# Power.net
KiCad netlist of a schematic drawn in Altium Designer
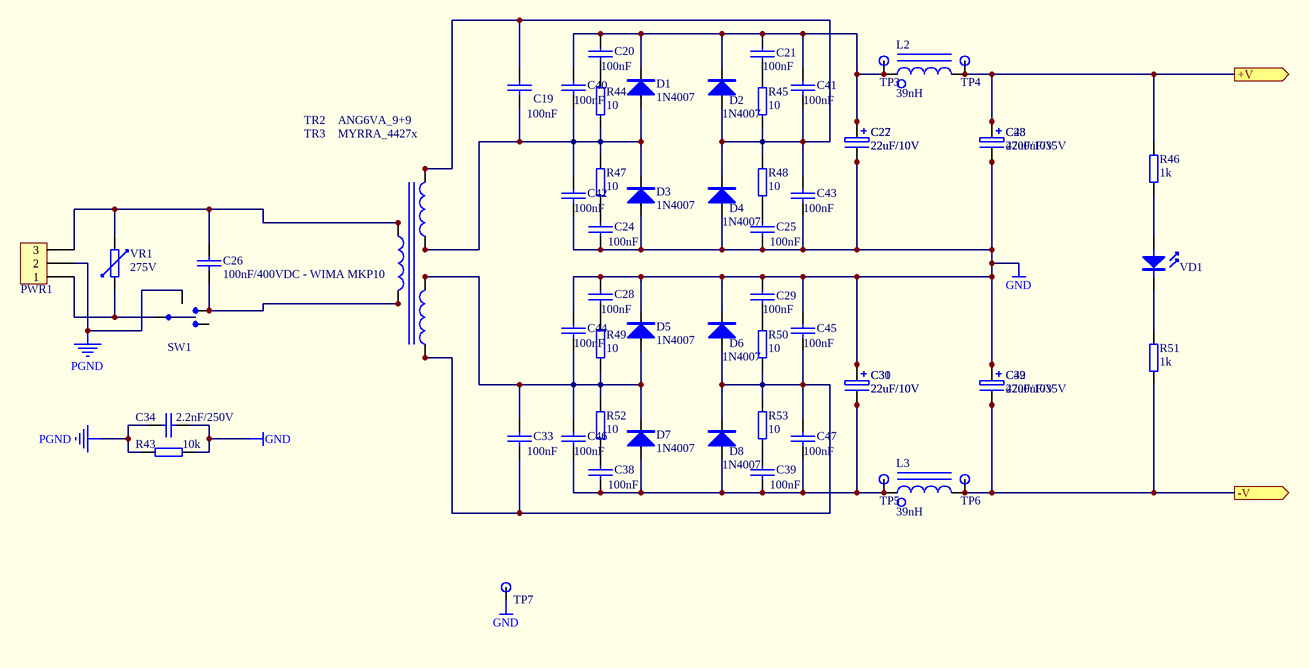
[diagram p0: Power.SchDoc]

(export (version "E")
  (design (tool "Eeschema 10.0.6"))
  (components
    (comp (ref "C19")
      (value "100nF")
      (footprint "CAP_C200-1")
      (description "Capacitor")
      (libsource (lib "ivan") (part "CAP"))
    )
    (comp (ref "C20")
      (value "100nF")
      (footprint "CAP_C200")
      (description "Capacitor")
      (libsource (lib "ivan") (part "CAP"))
    )
    (comp (ref "C21")
      (value "100nF")
      (footprint "CAP_C200")
      (description "Capacitor")
      (libsource (lib "ivan") (part "CAP"))
    )
    (comp (ref "C22")
      (value "22uF/10V")
      (footprint "CAP_EC10x20")
      (description "Electrolytic Capacitor")
      (libsource (lib "MainSchlib") (part "ELECTRO1"))
    )
    (comp (ref "C23")
      (value "4700uF/35V")
      (footprint "CAP_EC22x40")
      (description "Electrolytic Capacitor")
      (libsource (lib "ivan") (part "ELECTRO1"))
    )
    (comp (ref "C24")
      (value "100nF")
      (footprint "CAP_C200")
      (description "Capacitor")
      (libsource (lib "ivan") (part "CAP"))
    )
    (comp (ref "C25")
      (value "100nF")
      (footprint "CAP_C200")
      (description "Capacitor")
      (libsource (lib "ivan") (part "CAP"))
    )
    (comp (ref "C26")
      (value "100nF/400VDC - WIMA MKP10")
      (footprint "CAP_5.7x10.3RM7.5")
      (description "Capacitor")
      (libsource (lib "*") (part "CAP"))
    )
    (comp (ref "C27")
      (value "22uF/10V")
      (footprint "CAP_EC22x40")
      (description "Electrolytic Capacitor")
      (libsource (lib "MainSchlib") (part "ELECTRO1"))
    )
    (comp (ref "C28")
      (value "100nF")
      (footprint "CAP_C200")
      (description "Capacitor")
      (libsource (lib "ivan") (part "CAP"))
    )
    (comp (ref "C29")
      (value "100nF")
      (footprint "CAP_C200")
      (description "Capacitor")
      (libsource (lib "ivan") (part "CAP"))
    )
    (comp (ref "C30")
      (value "22uF/10V")
      (footprint "CAP_EC10x20")
      (description "Electrolytic Capacitor")
      (libsource (lib "MainSchlib") (part "ELECTRO1"))
    )
    (comp (ref "C31")
      (value "22uF/10V")
      (footprint "CAP_EC22x40")
      (description "Electrolytic Capacitor")
      (libsource (lib "MainSchlib") (part "ELECTRO1"))
    )
    (comp (ref "C32")
      (value "4700uF/35V")
      (footprint "CAP_EC22x40")
      (description "Electrolytic Capacitor")
      (libsource (lib "ivan") (part "ELECTRO1"))
    )
    (comp (ref "C33")
      (value "100nF")
      (footprint "CAP_C200-1")
      (description "Capacitor")
      (libsource (lib "ivan") (part "CAP"))
    )
    (comp (ref "C34")
      (value "2.2nF/250V")
      (footprint "CAP_5.7x10.3RM7.5")
      (description "Capacitor")
      (libsource (lib "*") (part "CAP"))
    )
    (comp (ref "C38")
      (value "100nF")
      (footprint "CAP_C200")
      (description "Capacitor")
      (libsource (lib "ivan") (part "CAP"))
    )
    (comp (ref "C39")
      (value "100nF")
      (footprint "CAP_C200")
      (description "Capacitor")
      (libsource (lib "ivan") (part "CAP"))
    )
    (comp (ref "C40")
      (value "100nF")
      (footprint "CAP_C200")
      (description "Capacitor")
      (libsource (lib "ivan") (part "CAP"))
    )
    (comp (ref "C41")
      (value "100nF")
      (footprint "CAP_C200")
      (description "Capacitor")
      (libsource (lib "ivan") (part "CAP"))
    )
    (comp (ref "C42")
      (value "100nF")
      (footprint "CAP_C200")
      (description "Capacitor")
      (libsource (lib "ivan") (part "CAP"))
    )
    (comp (ref "C43")
      (value "100nF")
      (footprint "CAP_C200")
      (description "Capacitor")
      (libsource (lib "ivan") (part "CAP"))
    )
    (comp (ref "C44")
      (value "100nF")
      (footprint "CAP_C200")
      (description "Capacitor")
      (libsource (lib "ivan") (part "CAP"))
    )
    (comp (ref "C45")
      (value "100nF")
      (footprint "CAP_C200")
      (description "Capacitor")
      (libsource (lib "ivan") (part "CAP"))
    )
    (comp (ref "C46")
      (value "100nF")
      (footprint "CAP_C200")
      (description "Capacitor")
      (libsource (lib "ivan") (part "CAP"))
    )
    (comp (ref "C47")
      (value "100nF")
      (footprint "CAP_C200")
      (description "Capacitor")
      (libsource (lib "ivan") (part "CAP"))
    )
    (comp (ref "C48")
      (value "22uF/10V")
      (footprint "CAP_EC10x20")
      (description "Electrolytic Capacitor")
      (libsource (lib "MainSchlib") (part "ELECTRO1"))
    )
    (comp (ref "C49")
      (value "22uF/10V")
      (footprint "CAP_EC10x20")
      (description "Electrolytic Capacitor")
      (libsource (lib "MainSchlib") (part "ELECTRO1"))
    )
    (comp (ref "D1")
      (value "1N4007")
      (footprint "DIODE_D400")
      (description "Diode")
      (libsource (lib "ivan") (part "DIODE"))
    )
    (comp (ref "D2")
      (value "1N4007")
      (footprint "DIODE_D400")
      (description "Diode")
      (libsource (lib "ivan") (part "DIODE"))
    )
    (comp (ref "D3")
      (value "1N4007")
      (footprint "DIODE_D400")
      (description "Diode")
      (libsource (lib "ivan") (part "DIODE"))
    )
    (comp (ref "D4")
      (value "1N4007")
      (footprint "DIODE_D400")
      (description "Diode")
      (libsource (lib "ivan") (part "DIODE"))
    )
    (comp (ref "D5")
      (value "1N4007")
      (footprint "DIODE_D400")
      (description "Diode")
      (libsource (lib "ivan") (part "DIODE"))
    )
    (comp (ref "D6")
      (value "1N4007")
      (footprint "DIODE_D400")
      (description "Diode")
      (libsource (lib "ivan") (part "DIODE"))
    )
    (comp (ref "D7")
      (value "1N4007")
      (footprint "DIODE_D400")
      (description "Diode")
      (libsource (lib "ivan") (part "DIODE"))
    )
    (comp (ref "D8")
      (value "1N4007")
      (footprint "DIODE_D400")
      (description "Diode")
      (libsource (lib "ivan") (part "DIODE"))
    )
    (comp (ref "L2")
      (value "39nH")
      (footprint "IND_SRI1205")
      (libsource (lib "MainSchlib") (part "INDUCTOR IRON1"))
    )
    (comp (ref "L3")
      (value "39nH")
      (footprint "IND_SRI1205")
      (libsource (lib "MainSchlib") (part "INDUCTOR IRON1"))
    )
    (comp (ref "PWR1")
      (value "CON3")
      (footprint "CON_TOP_3P")
      (description "Connector")
      (libsource (lib "*") (part "CON3"))
    )
    (comp (ref "R43")
      (value "10k")
      (footprint "RES_R400")
      (description "Resistor")
      (libsource (lib "*") (part "RES"))
    )
    (comp (ref "R44")
      (value "10")
      (footprint "RES_R400")
      (description "Resistor")
      (libsource (lib "*") (part "RES"))
    )
    (comp (ref "R45")
      (value "10")
      (footprint "RES_R400")
      (description "Resistor")
      (libsource (lib "*") (part "RES"))
    )
    (comp (ref "R46")
      (value "1k")
      (footprint "RES_R400")
      (description "Resistor")
      (libsource (lib "MainSchlib") (part "RES"))
    )
    (comp (ref "R47")
      (value "10")
      (footprint "RES_R400")
      (description "Resistor")
      (libsource (lib "*") (part "RES"))
    )
    (comp (ref "R48")
      (value "10")
      (footprint "RES_R400")
      (description "Resistor")
      (libsource (lib "*") (part "RES"))
    )
    (comp (ref "R49")
      (value "10")
      (footprint "RES_R400")
      (description "Resistor")
      (libsource (lib "*") (part "RES"))
    )
    (comp (ref "R50")
      (value "10")
      (footprint "RES_R400")
      (description "Resistor")
      (libsource (lib "*") (part "RES"))
    )
    (comp (ref "R51")
      (value "1k")
      (footprint "RES_R400")
      (description "Resistor")
      (libsource (lib "MainSchlib") (part "RES"))
    )
    (comp (ref "R52")
      (value "10")
      (footprint "RES_R400")
      (description "Resistor")
      (libsource (lib "*") (part "RES"))
    )
    (comp (ref "R53")
      (value "10")
      (footprint "RES_R400")
      (description "Resistor")
      (libsource (lib "*") (part "RES"))
    )
    (comp (ref "SW1") (value "SW") (footprint "SW_250VAC1.5A") (libsource (lib "*") (part "SW_2WAY")))
    (comp (ref "TP3")
      (value "TESTPAD")
      (footprint "MISC_PAD-36/65")
      (libsource (lib "MainSchlib") (part "TESTPAD"))
    )
    (comp (ref "TP4")
      (value "TESTPAD")
      (footprint "MISC_PAD-36/65")
      (libsource (lib "MainSchlib") (part "TESTPAD"))
    )
    (comp (ref "TP5")
      (value "TESTPAD")
      (footprint "MISC_PAD-36/65")
      (libsource (lib "MainSchlib") (part "TESTPAD"))
    )
    (comp (ref "TP6")
      (value "TESTPAD")
      (footprint "MISC_PAD-36/65")
      (libsource (lib "MainSchlib") (part "TESTPAD"))
    )
    (comp (ref "TP7")
      (value "TESTPAD")
      (footprint "MISC_PAD-36/65")
      (libsource (lib "MainSchlib") (part "TESTPAD"))
    )
    (comp (ref "TR2")
      (value "ANG6VA_9+9")
      (footprint "TRAF_ANG6VA")
      (libsource (lib "*") (part "TRAF_ANG6VAx+x"))
    )
    (comp (ref "TR3")
      (value "MYRRA_4427x")
      (footprint "TRAF_MYRRA_10VA")
      (libsource (lib "MainSchlib") (part "TRAF_MYRRA_10VA_D"))
    )
    (comp (ref "VD1")
      (value "LED")
      (footprint "LED_5MM")
      (description "LED, 3mm")
      (libsource (lib "MainSchlib") (part "LED"))
    )
    (comp (ref "VR1")
      (value "275V")
      (footprint "MISC_Varistor")
      (description "Resistor")
      (libsource (lib "*") (part "VARISTOR"))
    )
  )
  (nets
    (net (code "1") (name "/+V") (class "Default")
      (node (ref "C23") (pin "1") (pinfunction "1_1") (pintype "passive"))
      (node (ref "C48") (pin "1") (pinfunction "1_1") (pintype "passive"))
      (node (ref "L2") (pin "2") (pinfunction "2_2") (pintype "passive"))
      (node (ref "R46") (pin "2") (pintype "passive"))
      (node (ref "TP4") (pin "1") (pinfunction "1_1") (pintype "passive"))
    )
    (net (code "2") (name "/-V") (class "Default")
      (node (ref "C32") (pin "2") (pinfunction "2_2") (pintype "passive"))
      (node (ref "C49") (pin "2") (pinfunction "2_2") (pintype "passive"))
      (node (ref "L3") (pin "2") (pinfunction "2_2") (pintype "passive"))
      (node (ref "R51") (pin "1") (pintype "passive"))
      (node (ref "TP6") (pin "1") (pinfunction "1_1") (pintype "passive"))
    )
    (net (code "3") (name "GND") (class "Default")
      (node (ref "C22") (pin "2") (pinfunction "2_2") (pintype "passive"))
      (node (ref "C23") (pin "2") (pinfunction "2_2") (pintype "passive"))
      (node (ref "C24") (pin "2") (pinfunction "2_2") (pintype "passive"))
      (node (ref "C25") (pin "2") (pinfunction "2_2") (pintype "passive"))
      (node (ref "C27") (pin "2") (pinfunction "2_2") (pintype "passive"))
      (node (ref "C28") (pin "1") (pinfunction "1_1") (pintype "passive"))
      (node (ref "C29") (pin "1") (pinfunction "1_1") (pintype "passive"))
      (node (ref "C30") (pin "1") (pinfunction "1_1") (pintype "passive"))
      (node (ref "C31") (pin "1") (pinfunction "1_1") (pintype "passive"))
      (node (ref "C32") (pin "1") (pinfunction "1_1") (pintype "passive"))
      (node (ref "C34") (pin "2") (pinfunction "2_2") (pintype "passive"))
      (node (ref "C42") (pin "2") (pinfunction "2_2") (pintype "passive"))
      (node (ref "C43") (pin "2") (pinfunction "2_2") (pintype "passive"))
      (node (ref "C44") (pin "1") (pinfunction "1_1") (pintype "passive"))
      (node (ref "C45") (pin "1") (pinfunction "1_1") (pintype "passive"))
      (node (ref "C48") (pin "2") (pinfunction "2_2") (pintype "passive"))
      (node (ref "C49") (pin "1") (pinfunction "1_1") (pintype "passive"))
      (node (ref "D3") (pin "1") (pinfunction "A_1") (pintype "passive"))
      (node (ref "D4") (pin "1") (pinfunction "A_1") (pintype "passive"))
      (node (ref "D5") (pin "2") (pinfunction "K_2") (pintype "passive"))
      (node (ref "D6") (pin "2") (pinfunction "K_2") (pintype "passive"))
      (node (ref "R43") (pin "2") (pintype "passive"))
      (node (ref "TP7") (pin "1") (pinfunction "1_1") (pintype "passive"))
    )
    (net (code "4") (name "Net-(C20-Pad2)") (class "Default")
      (node (ref "C20") (pin "2") (pinfunction "2_2") (pintype "passive"))
      (node (ref "R44") (pin "2") (pintype "passive"))
    )
    (net (code "5") (name "Net-(C21-Pad2)") (class "Default")
      (node (ref "C21") (pin "2") (pinfunction "2_2") (pintype "passive"))
      (node (ref "R45") (pin "2") (pintype "passive"))
    )
    (net (code "6") (name "Net-(C24-Pad1)") (class "Default")
      (node (ref "C24") (pin "1") (pinfunction "1_1") (pintype "passive"))
      (node (ref "R47") (pin "1") (pintype "passive"))
    )
    (net (code "7") (name "Net-(C25-Pad1)") (class "Default")
      (node (ref "C25") (pin "1") (pinfunction "1_1") (pintype "passive"))
      (node (ref "R48") (pin "1") (pintype "passive"))
    )
    (net (code "8") (name "Net-(C26-Pad1)") (class "Default")
      (node (ref "C26") (pin "1") (pinfunction "1_1") (pintype "passive"))
      (node (ref "SW1") (pin "3") (pinfunction "3_3") (pintype "passive"))
      (node (ref "TR2") (pin "1") (pinfunction "1_1") (pintype "passive"))
      (node (ref "TR3") (pin "6") (pinfunction "6_6") (pintype "passive"))
    )
    (net (code "9") (name "Net-(C26-Pad2)") (class "Default")
      (node (ref "C26") (pin "2") (pinfunction "2_2") (pintype "passive"))
      (node (ref "PWR1") (pin "3") (pinfunction "3_3") (pintype "passive"))
      (node (ref "TR2") (pin "5") (pinfunction "5_5") (pintype "passive"))
      (node (ref "TR3") (pin "1") (pinfunction "1_1") (pintype "passive"))
      (node (ref "VR1") (pin "1") (pintype "passive"))
    )
    (net (code "10") (name "Net-(C28-Pad2)") (class "Default")
      (node (ref "C28") (pin "2") (pinfunction "2_2") (pintype "passive"))
      (node (ref "R49") (pin "2") (pintype "passive"))
    )
    (net (code "11") (name "Net-(C29-Pad2)") (class "Default")
      (node (ref "C29") (pin "2") (pinfunction "2_2") (pintype "passive"))
      (node (ref "R50") (pin "2") (pintype "passive"))
    )
    (net (code "12") (name "Net-(C38-Pad1)") (class "Default")
      (node (ref "C38") (pin "1") (pinfunction "1_1") (pintype "passive"))
      (node (ref "R52") (pin "1") (pintype "passive"))
    )
    (net (code "13") (name "Net-(C39-Pad1)") (class "Default")
      (node (ref "C39") (pin "1") (pinfunction "1_1") (pintype "passive"))
      (node (ref "R53") (pin "1") (pintype "passive"))
    )
    (net (code "14") (name "Net-(D1-A)") (class "Default")
      (node (ref "C19") (pin "2") (pinfunction "2_2") (pintype "passive"))
      (node (ref "C40") (pin "2") (pinfunction "2_2") (pintype "passive"))
      (node (ref "C42") (pin "1") (pinfunction "1_1") (pintype "passive"))
      (node (ref "D1") (pin "1") (pinfunction "A_1") (pintype "passive"))
      (node (ref "D3") (pin "2") (pinfunction "K_2") (pintype "passive"))
      (node (ref "R44") (pin "1") (pintype "passive"))
      (node (ref "R47") (pin "2") (pintype "passive"))
      (node (ref "TR2") (pin "9") (pinfunction "9_9") (pintype "passive"))
      (node (ref "TR3") (pin "11") (pinfunction "11_11") (pintype "passive"))
    )
    (net (code "15") (name "Net-(D1-K)") (class "Default")
      (node (ref "C20") (pin "1") (pinfunction "1_1") (pintype "passive"))
      (node (ref "C21") (pin "1") (pinfunction "1_1") (pintype "passive"))
      (node (ref "C22") (pin "1") (pinfunction "1_1") (pintype "passive"))
      (node (ref "C27") (pin "1") (pinfunction "1_1") (pintype "passive"))
      (node (ref "C40") (pin "1") (pinfunction "1_1") (pintype "passive"))
      (node (ref "C41") (pin "1") (pinfunction "1_1") (pintype "passive"))
      (node (ref "D1") (pin "2") (pinfunction "K_2") (pintype "passive"))
      (node (ref "D2") (pin "2") (pinfunction "K_2") (pintype "passive"))
      (node (ref "L2") (pin "1") (pinfunction "1_1") (pintype "passive"))
      (node (ref "TP3") (pin "1") (pinfunction "1_1") (pintype "passive"))
    )
    (net (code "16") (name "Net-(D2-A)") (class "Default")
      (node (ref "C19") (pin "1") (pinfunction "1_1") (pintype "passive"))
      (node (ref "C41") (pin "2") (pinfunction "2_2") (pintype "passive"))
      (node (ref "C43") (pin "1") (pinfunction "1_1") (pintype "passive"))
      (node (ref "D2") (pin "1") (pinfunction "A_1") (pintype "passive"))
      (node (ref "D4") (pin "2") (pinfunction "K_2") (pintype "passive"))
      (node (ref "R45") (pin "1") (pintype "passive"))
      (node (ref "R48") (pin "2") (pintype "passive"))
      (node (ref "TR2") (pin "10") (pinfunction "10_10") (pintype "passive"))
      (node (ref "TR3") (pin "12") (pinfunction "12_12") (pintype "passive"))
    )
    (net (code "17") (name "Net-(D5-A)") (class "Default")
      (node (ref "C33") (pin "1") (pinfunction "1_1") (pintype "passive"))
      (node (ref "C44") (pin "2") (pinfunction "2_2") (pintype "passive"))
      (node (ref "C46") (pin "1") (pinfunction "1_1") (pintype "passive"))
      (node (ref "D5") (pin "1") (pinfunction "A_1") (pintype "passive"))
      (node (ref "D7") (pin "2") (pinfunction "K_2") (pintype "passive"))
      (node (ref "R49") (pin "1") (pintype "passive"))
      (node (ref "R52") (pin "2") (pintype "passive"))
      (node (ref "TR2") (pin "7") (pinfunction "7_7") (pintype "passive"))
      (node (ref "TR3") (pin "8") (pinfunction "8_8") (pintype "passive"))
    )
    (net (code "18") (name "Net-(D6-A)") (class "Default")
      (node (ref "C33") (pin "2") (pinfunction "2_2") (pintype "passive"))
      (node (ref "C45") (pin "2") (pinfunction "2_2") (pintype "passive"))
      (node (ref "C47") (pin "1") (pinfunction "1_1") (pintype "passive"))
      (node (ref "D6") (pin "1") (pinfunction "A_1") (pintype "passive"))
      (node (ref "D8") (pin "2") (pinfunction "K_2") (pintype "passive"))
      (node (ref "R50") (pin "1") (pintype "passive"))
      (node (ref "R53") (pin "2") (pintype "passive"))
      (node (ref "TR2") (pin "6") (pinfunction "6_6") (pintype "passive"))
      (node (ref "TR3") (pin "7") (pinfunction "7_7") (pintype "passive"))
    )
    (net (code "19") (name "Net-(D7-A)") (class "Default")
      (node (ref "C30") (pin "2") (pinfunction "2_2") (pintype "passive"))
      (node (ref "C31") (pin "2") (pinfunction "2_2") (pintype "passive"))
      (node (ref "C38") (pin "2") (pinfunction "2_2") (pintype "passive"))
      (node (ref "C39") (pin "2") (pinfunction "2_2") (pintype "passive"))
      (node (ref "C46") (pin "2") (pinfunction "2_2") (pintype "passive"))
      (node (ref "C47") (pin "2") (pinfunction "2_2") (pintype "passive"))
      (node (ref "D7") (pin "1") (pinfunction "A_1") (pintype "passive"))
      (node (ref "D8") (pin "1") (pinfunction "A_1") (pintype "passive"))
      (node (ref "L3") (pin "1") (pinfunction "1_1") (pintype "passive"))
      (node (ref "TP5") (pin "1") (pinfunction "1_1") (pintype "passive"))
    )
    (net (code "20") (name "Net-(PWR1-Pad1)") (class "Default")
      (node (ref "PWR1") (pin "1") (pinfunction "1_1") (pintype "passive"))
      (node (ref "SW1") (pin "2") (pinfunction "2_2") (pintype "passive"))
      (node (ref "VR1") (pin "2") (pintype "passive"))
    )
    (net (code "21") (name "Net-(VD1-A1)") (class "Default")
      (node (ref "R46") (pin "1") (pintype "passive"))
      (node (ref "VD1") (pin "1") (pinfunction "A1_1") (pintype "passive"))
    )
    (net (code "22") (name "Net-(VD1-K)") (class "Default")
      (node (ref "R51") (pin "2") (pintype "passive"))
      (node (ref "VD1") (pin "2") (pinfunction "K_2") (pintype "passive"))
    )
    (net (code "23") (name "PGND") (class "Default")
      (node (ref "C34") (pin "1") (pinfunction "1_1") (pintype "passive"))
      (node (ref "PWR1") (pin "2") (pinfunction "2_2") (pintype "passive"))
      (node (ref "R43") (pin "1") (pintype "passive"))
      (node (ref "SW1") (pin "0") (pinfunction "0_0") (pintype "passive"))
    )
    (net (code "24") (name "unconnected-(SW1-Pad1)") (class "Default")
      (node (ref "SW1") (pin "1") (pinfunction "1_1") (pintype "passive"))
    )
  )
)
